# POWER.net
KiCad netlist of a schematic drawn in Altium Designer
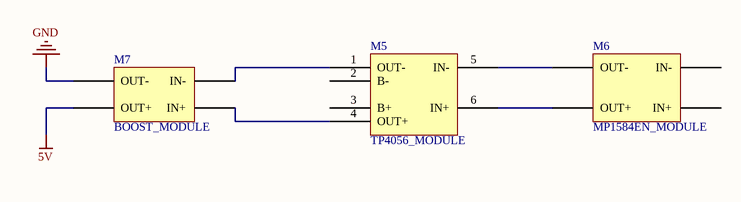
[diagram p0: POWER.SchDoc]

(export (version "E")
  (design (tool "Eeschema 10.0.6"))
  (components
    (comp (ref "M5")
      (value "TP4056_MODULE")
      (footprint "TP4056_MODULE")
      (libsource (lib "KHOEMACH_LIB") (part "TP4056_MODULE"))
    )
    (comp (ref "M6")
      (value "MP1584EN_MODULE")
      (footprint "MP1584EN_MODULE")
      (libsource (lib "KHOEMACH_LIB") (part "MP1584EN_MODULE"))
    )
    (comp (ref "M7")
      (value "BOOST_MODULE")
      (footprint "BOOST_MODULE_MINI")
      (libsource (lib "KHOEMACH_LIB") (part "BOOST_MODULE"))
    )
  )
  (nets
    (net (code "1") (name "5V") (class "Default")
      (node (ref "M7") (pin "3") (pinfunction "OUT+_3") (pintype "passive"))
    )
    (net (code "2") (name "GND") (class "Default")
      (node (ref "M7") (pin "4") (pinfunction "OUT-_4") (pintype "passive"))
    )
    (net (code "3") (name "Net-(M5-IN+)") (class "Default")
      (node (ref "M5") (pin "6") (pinfunction "IN+_6") (pintype "passive"))
      (node (ref "M6") (pin "3") (pinfunction "OUT+_3") (pintype "passive"))
    )
    (net (code "4") (name "Net-(M5-IN-)") (class "Default")
      (node (ref "M5") (pin "5") (pinfunction "IN-_5") (pintype "passive"))
      (node (ref "M6") (pin "4") (pinfunction "OUT-_4") (pintype "passive"))
    )
    (net (code "5") (name "Net-(M5-OUT+)") (class "Default")
      (node (ref "M5") (pin "4") (pinfunction "OUT+_4") (pintype "passive"))
      (node (ref "M7") (pin "1") (pinfunction "IN+_1") (pintype "passive"))
    )
    (net (code "6") (name "Net-(M5-OUT-)") (class "Default")
      (node (ref "M5") (pin "1") (pinfunction "OUT-_1") (pintype "passive"))
      (node (ref "M7") (pin "2") (pinfunction "IN-_2") (pintype "passive"))
    )
    (net (code "7") (name "unconnected-(M5-B+-Pad3)") (class "Default")
      (node (ref "M5") (pin "3") (pinfunction "B+_3") (pintype "passive"))
    )
    (net (code "8") (name "unconnected-(M5-B--Pad2)") (class "Default")
      (node (ref "M5") (pin "2") (pinfunction "B-_2") (pintype "passive"))
    )
    (net (code "9") (name "unconnected-(M6-IN+-Pad1)") (class "Default")
      (node (ref "M6") (pin "1") (pinfunction "IN+_1") (pintype "passive"))
    )
    (net (code "10") (name "unconnected-(M6-IN--Pad2)") (class "Default")
      (node (ref "M6") (pin "2") (pinfunction "IN-_2") (pintype "passive"))
    )
  )
)
